# 40Ortho.net
KiCad netlist of a schematic drawn in EAGLE
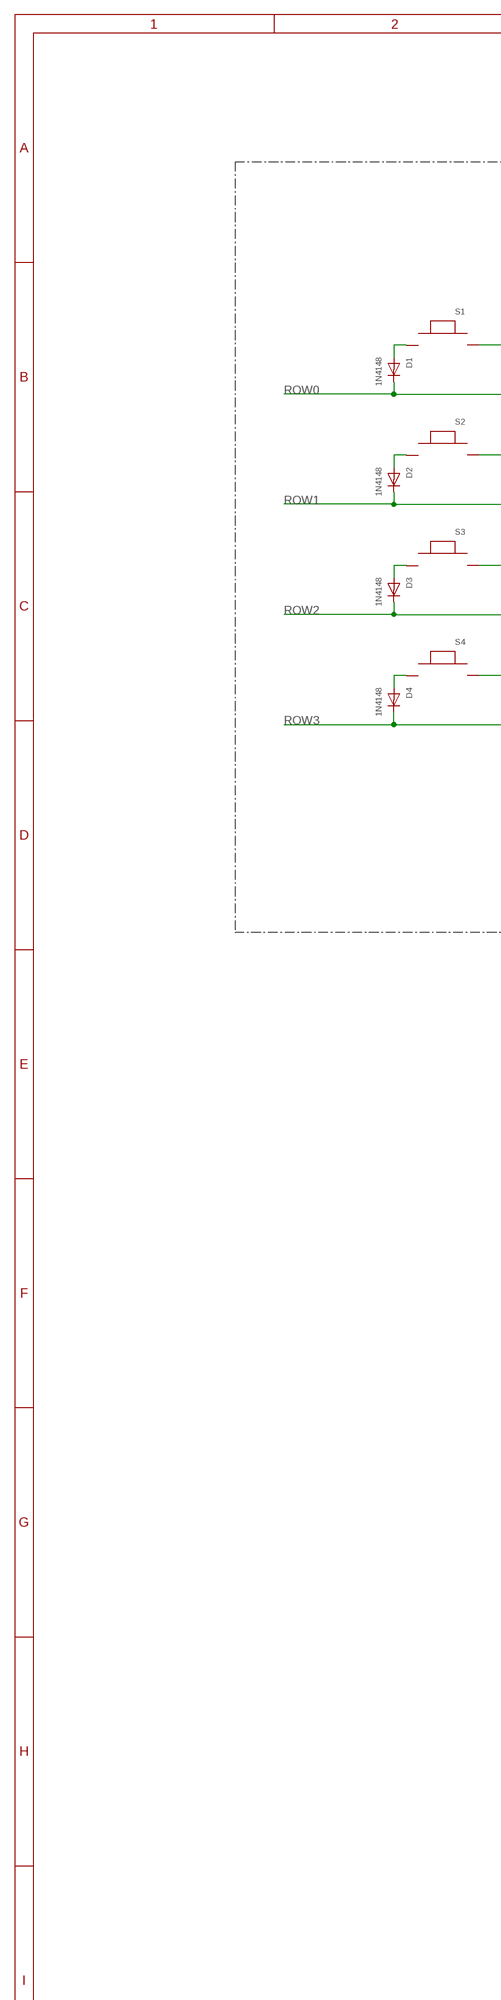
[diagram p0: schematic, sheet 1, part 1 of 2]
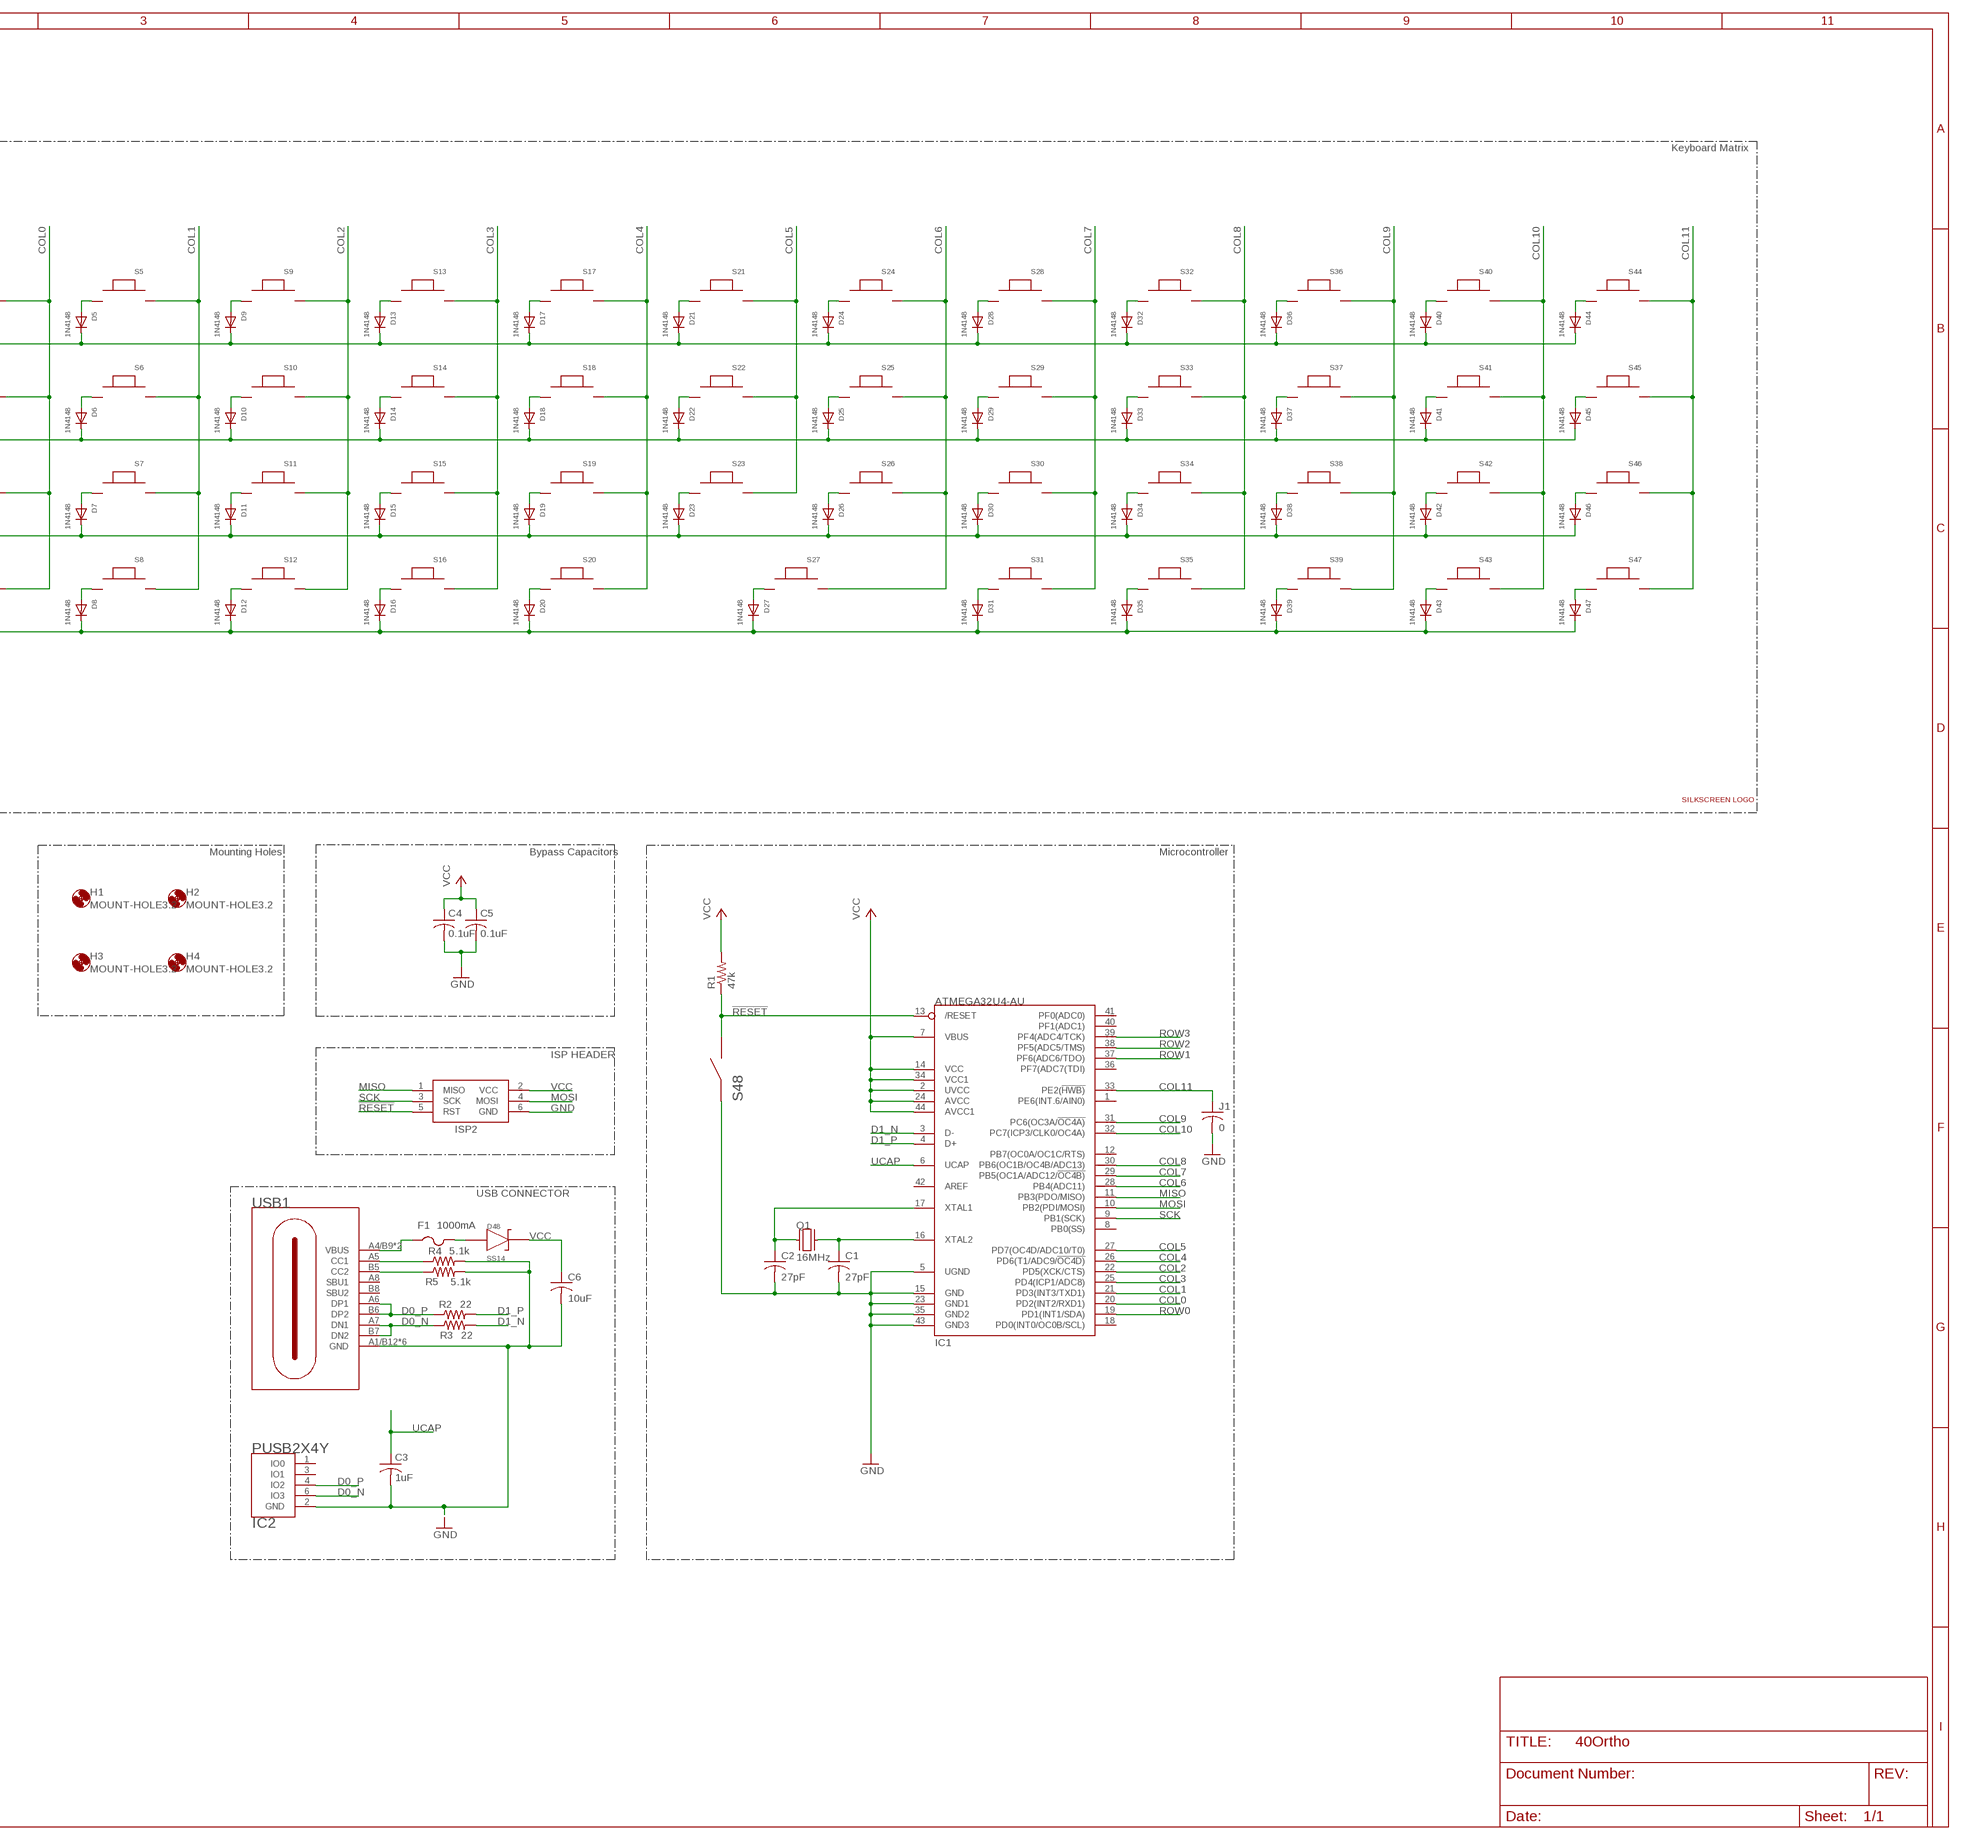
[diagram p1: schematic, sheet 1, part 2 of 2]

(export (version "E")
  (design (tool "Eeschema 10.0.6"))
  (components
    (comp (ref "C1")
      (value "27pF")
      (footprint "eagle-import:C0805")
      (libsource (lib "eagle-import") (part "C-USC0805"))
    )
    (comp (ref "C2")
      (value "27pF")
      (footprint "eagle-import:C0805")
      (libsource (lib "eagle-import") (part "C-USC0805"))
    )
    (comp (ref "C3")
      (value "1uF")
      (footprint "eagle-import:C0805")
      (libsource (lib "eagle-import") (part "C-USC0805"))
    )
    (comp (ref "C4")
      (value "0.1uF")
      (footprint "eagle-import:C0805")
      (libsource (lib "eagle-import") (part "C-USC0805"))
    )
    (comp (ref "C5")
      (value "0.1uF")
      (footprint "eagle-import:C0805")
      (libsource (lib "eagle-import") (part "C-USC0805"))
    )
    (comp (ref "C6")
      (value "10uF")
      (footprint "eagle-import:C0805")
      (libsource (lib "eagle-import") (part "C-USC0805"))
    )
    (comp (ref "D1")
      (value "1N4148")
      (footprint "eagle-import:SOD-323F")
      (fields (field (name "SPICEPREFIX") "D"))
      (libsource (lib "eagle-import") (part "DIODESOD-323F"))
    )
    (comp (ref "D2")
      (value "1N4148")
      (footprint "eagle-import:SOD-323F")
      (libsource (lib "eagle-import") (part "DIODESOD-323F"))
    )
    (comp (ref "D3")
      (value "1N4148")
      (footprint "eagle-import:SOD-323F")
      (libsource (lib "eagle-import") (part "DIODESOD-323F"))
    )
    (comp (ref "D4")
      (value "1N4148")
      (footprint "eagle-import:SOD-323F")
      (libsource (lib "eagle-import") (part "DIODESOD-323F"))
    )
    (comp (ref "D5")
      (value "1N4148")
      (footprint "eagle-import:SOD-323F")
      (libsource (lib "eagle-import") (part "DIODESOD-323F"))
    )
    (comp (ref "D6")
      (value "1N4148")
      (footprint "eagle-import:SOD-323F")
      (fields (field (name "SPICEPREFIX") "D"))
      (libsource (lib "eagle-import") (part "DIODESOD-323F"))
    )
    (comp (ref "D7")
      (value "1N4148")
      (footprint "eagle-import:SOD-323F")
      (libsource (lib "eagle-import") (part "DIODESOD-323F"))
    )
    (comp (ref "D8")
      (value "1N4148")
      (footprint "eagle-import:SOD-323F")
      (libsource (lib "eagle-import") (part "DIODESOD-323F"))
    )
    (comp (ref "D9")
      (value "1N4148")
      (footprint "eagle-import:SOD-323F")
      (libsource (lib "eagle-import") (part "DIODESOD-323F"))
    )
    (comp (ref "D10")
      (value "1N4148")
      (footprint "eagle-import:SOD-323F")
      (libsource (lib "eagle-import") (part "DIODESOD-323F"))
    )
    (comp (ref "D11")
      (value "1N4148")
      (footprint "eagle-import:SOD-323F")
      (libsource (lib "eagle-import") (part "DIODESOD-323F"))
    )
    (comp (ref "D12")
      (value "1N4148")
      (footprint "eagle-import:SOD-323F")
      (libsource (lib "eagle-import") (part "DIODESOD-323F"))
    )
    (comp (ref "D13")
      (value "1N4148")
      (footprint "eagle-import:SOD-323F")
      (libsource (lib "eagle-import") (part "DIODESOD-323F"))
    )
    (comp (ref "D14")
      (value "1N4148")
      (footprint "eagle-import:SOD-323F")
      (libsource (lib "eagle-import") (part "DIODESOD-323F"))
    )
    (comp (ref "D15")
      (value "1N4148")
      (footprint "eagle-import:SOD-323F")
      (libsource (lib "eagle-import") (part "DIODESOD-323F"))
    )
    (comp (ref "D16")
      (value "1N4148")
      (footprint "eagle-import:SOD-323F")
      (libsource (lib "eagle-import") (part "DIODESOD-323F"))
    )
    (comp (ref "D17")
      (value "1N4148")
      (footprint "eagle-import:SOD-323F")
      (libsource (lib "eagle-import") (part "DIODESOD-323F"))
    )
    (comp (ref "D18")
      (value "1N4148")
      (footprint "eagle-import:SOD-323F")
      (libsource (lib "eagle-import") (part "DIODESOD-323F"))
    )
    (comp (ref "D19")
      (value "1N4148")
      (footprint "eagle-import:SOD-323F")
      (libsource (lib "eagle-import") (part "DIODESOD-323F"))
    )
    (comp (ref "D20")
      (value "1N4148")
      (footprint "eagle-import:SOD-323F")
      (libsource (lib "eagle-import") (part "DIODESOD-323F"))
    )
    (comp (ref "D21")
      (value "1N4148")
      (footprint "eagle-import:SOD-323F")
      (libsource (lib "eagle-import") (part "DIODESOD-323F"))
    )
    (comp (ref "D22")
      (value "1N4148")
      (footprint "eagle-import:SOD-323F")
      (libsource (lib "eagle-import") (part "DIODESOD-323F"))
    )
    (comp (ref "D23")
      (value "1N4148")
      (footprint "eagle-import:SOD-323F")
      (libsource (lib "eagle-import") (part "DIODESOD-323F"))
    )
    (comp (ref "D24")
      (value "1N4148")
      (footprint "eagle-import:SOD-323F")
      (libsource (lib "eagle-import") (part "DIODESOD-323F"))
    )
    (comp (ref "D25")
      (value "1N4148")
      (footprint "eagle-import:SOD-323F")
      (libsource (lib "eagle-import") (part "DIODESOD-323F"))
    )
    (comp (ref "D26")
      (value "1N4148")
      (footprint "eagle-import:SOD-323F")
      (libsource (lib "eagle-import") (part "DIODESOD-323F"))
    )
    (comp (ref "D27")
      (value "1N4148")
      (footprint "eagle-import:SOD-323F")
      (libsource (lib "eagle-import") (part "DIODESOD-323F"))
    )
    (comp (ref "D28")
      (value "1N4148")
      (footprint "eagle-import:SOD-323F")
      (libsource (lib "eagle-import") (part "DIODESOD-323F"))
    )
    (comp (ref "D29")
      (value "1N4148")
      (footprint "eagle-import:SOD-323F")
      (libsource (lib "eagle-import") (part "DIODESOD-323F"))
    )
    (comp (ref "D30")
      (value "1N4148")
      (footprint "eagle-import:SOD-323F")
      (libsource (lib "eagle-import") (part "DIODESOD-323F"))
    )
    (comp (ref "D31")
      (value "1N4148")
      (footprint "eagle-import:SOD-323F")
      (libsource (lib "eagle-import") (part "DIODESOD-323F"))
    )
    (comp (ref "D32")
      (value "1N4148")
      (footprint "eagle-import:SOD-323F")
      (libsource (lib "eagle-import") (part "DIODESOD-323F"))
    )
    (comp (ref "D33")
      (value "1N4148")
      (footprint "eagle-import:SOD-323F")
      (libsource (lib "eagle-import") (part "DIODESOD-323F"))
    )
    (comp (ref "D34")
      (value "1N4148")
      (footprint "eagle-import:SOD-323F")
      (libsource (lib "eagle-import") (part "DIODESOD-323F"))
    )
    (comp (ref "D35")
      (value "1N4148")
      (footprint "eagle-import:SOD-323F")
      (libsource (lib "eagle-import") (part "DIODESOD-323F"))
    )
    (comp (ref "D36")
      (value "1N4148")
      (footprint "eagle-import:SOD-323F")
      (libsource (lib "eagle-import") (part "DIODESOD-323F"))
    )
    (comp (ref "D37")
      (value "1N4148")
      (footprint "eagle-import:SOD-323F")
      (libsource (lib "eagle-import") (part "DIODESOD-323F"))
    )
    (comp (ref "D38")
      (value "1N4148")
      (footprint "eagle-import:SOD-323F")
      (libsource (lib "eagle-import") (part "DIODESOD-323F"))
    )
    (comp (ref "D39")
      (value "1N4148")
      (footprint "eagle-import:SOD-323F")
      (libsource (lib "eagle-import") (part "DIODESOD-323F"))
    )
    (comp (ref "D40")
      (value "1N4148")
      (footprint "eagle-import:SOD-323F")
      (libsource (lib "eagle-import") (part "DIODESOD-323F"))
    )
    (comp (ref "D41")
      (value "1N4148")
      (footprint "eagle-import:SOD-323F")
      (libsource (lib "eagle-import") (part "DIODESOD-323F"))
    )
    (comp (ref "D42")
      (value "1N4148")
      (footprint "eagle-import:SOD-323F")
      (libsource (lib "eagle-import") (part "DIODESOD-323F"))
    )
    (comp (ref "D43")
      (value "1N4148")
      (footprint "eagle-import:SOD-323F")
      (libsource (lib "eagle-import") (part "DIODESOD-323F"))
    )
    (comp (ref "D44")
      (value "1N4148")
      (footprint "eagle-import:SOD-323F")
      (libsource (lib "eagle-import") (part "DIODESOD-323F"))
    )
    (comp (ref "D45")
      (value "1N4148")
      (footprint "eagle-import:SOD-323F")
      (libsource (lib "eagle-import") (part "DIODESOD-323F"))
    )
    (comp (ref "D46")
      (value "1N4148")
      (footprint "eagle-import:SOD-323F")
      (libsource (lib "eagle-import") (part "DIODESOD-323F"))
    )
    (comp (ref "D47")
      (value "1N4148")
      (footprint "eagle-import:SOD-323F")
      (libsource (lib "eagle-import") (part "DIODESOD-323F"))
    )
    (comp (ref "D48")
      (value "SS14")
      (footprint "eagle-import:DO-214AC")
      (libsource (lib "eagle-import") (part "SS14"))
    )
    (comp (ref "F1")
      (value "1000mA")
      (footprint "eagle-import:R1206")
      (libsource (lib "eagle-import") (part "PTCFUSE-1206"))
    )
    (comp (ref "H1")
      (value "MOUNT-HOLE3.2")
      (footprint "eagle-import:3,2")
      (libsource (lib "eagle-import") (part "MOUNT-HOLE3.2"))
    )
    (comp (ref "H2")
      (value "MOUNT-HOLE3.2")
      (footprint "eagle-import:3,2")
      (libsource (lib "eagle-import") (part "MOUNT-HOLE3.2"))
    )
    (comp (ref "H3")
      (value "MOUNT-HOLE3.2")
      (footprint "eagle-import:3,2")
      (libsource (lib "eagle-import") (part "MOUNT-HOLE3.2"))
    )
    (comp (ref "H4")
      (value "MOUNT-HOLE3.2")
      (footprint "eagle-import:3,2")
      (libsource (lib "eagle-import") (part "MOUNT-HOLE3.2"))
    )
    (comp (ref "IC1")
      (value "ATMEGA32U4-AU")
      (footprint "eagle-import:TQFP44")
      (libsource (lib "eagle-import") (part "ATMEGA32U4-AU"))
    )
    (comp (ref "IC2")
      (value "PUSB2X4Y")
      (footprint "eagle-import:SOT363")
      (libsource (lib "eagle-import") (part "PUSB2X4Y"))
    )
    (comp (ref "ISP2")
      (value "AVRISP-6")
      (footprint "eagle-import:AVRISP")
      (libsource (lib "eagle-import") (part "AVRISP-6"))
    )
    (comp (ref "J1")
      (value "0")
      (footprint "eagle-import:C0805")
      (libsource (lib "eagle-import") (part "C-USC0805"))
    )
    (comp (ref "Q1")
      (value "16MHz")
      (footprint "eagle-import:ABLS7M2")
      (libsource (lib "eagle-import") (part "ABLS7M2"))
    )
    (comp (ref "R1")
      (value "47k")
      (footprint "eagle-import:R0805")
      (libsource (lib "eagle-import") (part "R-US_R0805"))
    )
    (comp (ref "R2")
      (value "22")
      (footprint "eagle-import:R0805")
      (libsource (lib "eagle-import") (part "R-US_R0805"))
    )
    (comp (ref "R3")
      (value "22")
      (footprint "eagle-import:R0805")
      (libsource (lib "eagle-import") (part "R-US_R0805"))
    )
    (comp (ref "R4")
      (value "5.1k")
      (footprint "eagle-import:R0805")
      (libsource (lib "eagle-import") (part "R-US_R0805"))
    )
    (comp (ref "R5")
      (value "5.1k")
      (footprint "eagle-import:R0805")
      (libsource (lib "eagle-import") (part "R-US_R0805"))
    )
    (comp (ref "S1")
      (value "MX_SMD_1U")
      (footprint "eagle-import:MX_SMD")
      (libsource (lib "eagle-import") (part "MX_SMD_1U"))
    )
    (comp (ref "S2")
      (value "MX_SMD_1U")
      (footprint "eagle-import:MX_SMD")
      (libsource (lib "eagle-import") (part "MX_SMD_1U"))
    )
    (comp (ref "S3")
      (value "MX_SMD_1U")
      (footprint "eagle-import:MX_SMD")
      (libsource (lib "eagle-import") (part "MX_SMD_1U"))
    )
    (comp (ref "S4")
      (value "MX_SMD_1U")
      (footprint "eagle-import:MX_SMD")
      (libsource (lib "eagle-import") (part "MX_SMD_1U"))
    )
    (comp (ref "S5")
      (value "MX_SMD_1U")
      (footprint "eagle-import:MX_SMD")
      (libsource (lib "eagle-import") (part "MX_SMD_1U"))
    )
    (comp (ref "S6")
      (value "MX_SMD_1U")
      (footprint "eagle-import:MX_SMD")
      (libsource (lib "eagle-import") (part "MX_SMD_1U"))
    )
    (comp (ref "S7")
      (value "MX_SMD_1U")
      (footprint "eagle-import:MX_SMD")
      (libsource (lib "eagle-import") (part "MX_SMD_1U"))
    )
    (comp (ref "S8")
      (value "MX_SMD_1U")
      (footprint "eagle-import:MX_SMD")
      (libsource (lib "eagle-import") (part "MX_SMD_1U"))
    )
    (comp (ref "S9")
      (value "MX_SMD_1U")
      (footprint "eagle-import:MX_SMD")
      (libsource (lib "eagle-import") (part "MX_SMD_1U"))
    )
    (comp (ref "S10")
      (value "MX_SMD_1U")
      (footprint "eagle-import:MX_SMD")
      (libsource (lib "eagle-import") (part "MX_SMD_1U"))
    )
    (comp (ref "S11")
      (value "MX_SMD_1U")
      (footprint "eagle-import:MX_SMD")
      (libsource (lib "eagle-import") (part "MX_SMD_1U"))
    )
    (comp (ref "S12")
      (value "MX_SMD_1U")
      (footprint "eagle-import:MX_SMD")
      (libsource (lib "eagle-import") (part "MX_SMD_1U"))
    )
    (comp (ref "S13")
      (value "MX_SMD_1U")
      (footprint "eagle-import:MX_SMD")
      (libsource (lib "eagle-import") (part "MX_SMD_1U"))
    )
    (comp (ref "S14")
      (value "MX_SMD_1U")
      (footprint "eagle-import:MX_SMD")
      (libsource (lib "eagle-import") (part "MX_SMD_1U"))
    )
    (comp (ref "S15")
      (value "MX_SMD_1U")
      (footprint "eagle-import:MX_SMD")
      (libsource (lib "eagle-import") (part "MX_SMD_1U"))
    )
    (comp (ref "S16")
      (value "MX_SMD_1U")
      (footprint "eagle-import:MX_SMD")
      (libsource (lib "eagle-import") (part "MX_SMD_1U"))
    )
    (comp (ref "S17")
      (value "MX_SMD_1U")
      (footprint "eagle-import:MX_SMD")
      (libsource (lib "eagle-import") (part "MX_SMD_1U"))
    )
    (comp (ref "S18")
      (value "MX_SMD_1U")
      (footprint "eagle-import:MX_SMD")
      (libsource (lib "eagle-import") (part "MX_SMD_1U"))
    )
    (comp (ref "S19")
      (value "MX_SMD_1U")
      (footprint "eagle-import:MX_SMD")
      (libsource (lib "eagle-import") (part "MX_SMD_1U"))
    )
    (comp (ref "S20")
      (value "MX_SMD_1U")
      (footprint "eagle-import:MX_SMD")
      (libsource (lib "eagle-import") (part "MX_SMD_1U"))
    )
    (comp (ref "S21")
      (value "MX_SMD_1U")
      (footprint "eagle-import:MX_SMD")
      (libsource (lib "eagle-import") (part "MX_SMD_1U"))
    )
    (comp (ref "S22")
      (value "MX_SMD_1U")
      (footprint "eagle-import:MX_SMD")
      (libsource (lib "eagle-import") (part "MX_SMD_1U"))
    )
    (comp (ref "S23")
      (value "MX_SMD_1U")
      (footprint "eagle-import:MX_SMD")
      (libsource (lib "eagle-import") (part "MX_SMD_1U"))
    )
    (comp (ref "S24")
      (value "MX_SMD_1U")
      (footprint "eagle-import:MX_SMD")
      (libsource (lib "eagle-import") (part "MX_SMD_1U"))
    )
    (comp (ref "S25")
      (value "MX_SMD_1U")
      (footprint "eagle-import:MX_SMD")
      (libsource (lib "eagle-import") (part "MX_SMD_1U"))
    )
    (comp (ref "S26")
      (value "MX_SMD_1U")
      (footprint "eagle-import:MX_SMD")
      (libsource (lib "eagle-import") (part "MX_SMD_1U"))
    )
    (comp (ref "S27")
      (value "MX_SMD_2UH")
      (footprint "eagle-import:MX_SMD2U")
      (libsource (lib "eagle-import") (part "MX_SMD_2UH"))
    )
    (comp (ref "S28")
      (value "MX_SMD_1U")
      (footprint "eagle-import:MX_SMD")
      (libsource (lib "eagle-import") (part "MX_SMD_1U"))
    )
    (comp (ref "S29")
      (value "MX_SMD_1U")
      (footprint "eagle-import:MX_SMD")
      (libsource (lib "eagle-import") (part "MX_SMD_1U"))
    )
    (comp (ref "S30")
      (value "MX_SMD_1U")
      (footprint "eagle-import:MX_SMD")
      (libsource (lib "eagle-import") (part "MX_SMD_1U"))
    )
    (comp (ref "S31")
      (value "MX_SMD_1U")
      (footprint "eagle-import:MX_SMD")
      (libsource (lib "eagle-import") (part "MX_SMD_1U"))
    )
    (comp (ref "S32")
      (value "MX_SMD_1U")
      (footprint "eagle-import:MX_SMD")
      (libsource (lib "eagle-import") (part "MX_SMD_1U"))
    )
    (comp (ref "S33")
      (value "MX_SMD_1U")
      (footprint "eagle-import:MX_SMD")
      (libsource (lib "eagle-import") (part "MX_SMD_1U"))
    )
    (comp (ref "S34")
      (value "MX_SMD_1U")
      (footprint "eagle-import:MX_SMD")
      (libsource (lib "eagle-import") (part "MX_SMD_1U"))
    )
    (comp (ref "S35")
      (value "MX_SMD_1U")
      (footprint "eagle-import:MX_SMD")
      (libsource (lib "eagle-import") (part "MX_SMD_1U"))
    )
    (comp (ref "S36")
      (value "MX_SMD_1U")
      (footprint "eagle-import:MX_SMD")
      (libsource (lib "eagle-import") (part "MX_SMD_1U"))
    )
    (comp (ref "S37")
      (value "MX_SMD_1U")
      (footprint "eagle-import:MX_SMD")
      (libsource (lib "eagle-import") (part "MX_SMD_1U"))
    )
    (comp (ref "S38")
      (value "MX_SMD_1U")
      (footprint "eagle-import:MX_SMD")
      (libsource (lib "eagle-import") (part "MX_SMD_1U"))
    )
    (comp (ref "S39")
      (value "MX_SMD_1U")
      (footprint "eagle-import:MX_SMD")
      (libsource (lib "eagle-import") (part "MX_SMD_1U"))
    )
    (comp (ref "S40")
      (value "MX_SMD_1U")
      (footprint "eagle-import:MX_SMD")
      (libsource (lib "eagle-import") (part "MX_SMD_1U"))
    )
    (comp (ref "S41")
      (value "MX_SMD_1U")
      (footprint "eagle-import:MX_SMD")
      (libsource (lib "eagle-import") (part "MX_SMD_1U"))
    )
    (comp (ref "S42")
      (value "MX_SMD_1U")
      (footprint "eagle-import:MX_SMD")
      (libsource (lib "eagle-import") (part "MX_SMD_1U"))
    )
    (comp (ref "S43")
      (value "MX_SMD_1U")
      (footprint "eagle-import:MX_SMD")
      (libsource (lib "eagle-import") (part "MX_SMD_1U"))
    )
    (comp (ref "S44")
      (value "MX_SMD_1U")
      (footprint "eagle-import:MX_SMD")
      (libsource (lib "eagle-import") (part "MX_SMD_1U"))
    )
    (comp (ref "S45")
      (value "MX_SMD_1U")
      (footprint "eagle-import:MX_SMD")
      (libsource (lib "eagle-import") (part "MX_SMD_1U"))
    )
    (comp (ref "S46")
      (value "MX_SMD_1U")
      (footprint "eagle-import:MX_SMD")
      (libsource (lib "eagle-import") (part "MX_SMD_1U"))
    )
    (comp (ref "S47")
      (value "MX_SMD_1U")
      (footprint "eagle-import:MX_SMD")
      (libsource (lib "eagle-import") (part "MX_SMD_1U"))
    )
    (comp (ref "S48")
      (value "B3U-1000P")
      (footprint "eagle-import:B3U-1000P")
      (libsource (lib "eagle-import") (part "B3U-1000P"))
    )
    (comp (ref "U$1")
      (value "LOGO")
      (footprint "eagle-import:LOGO")
      (libsource (lib "eagle-import") (part "LOGO"))
    )
    (comp (ref "USB1")
      (value "USBC_16PINSMD")
      (footprint "eagle-import:USBC_16PINSMD")
      (libsource (lib "eagle-import") (part "USBC_16PINSMD"))
    )
  )
  (nets
    (net (code "1") (name "/COL0") (class "Default")
      (node (ref "IC1") (pin "20") (pinfunction "PD2(INT2/RXD1)_20") (pintype "bidirectional"))
      (node (ref "S1") (pin "P$2") (pinfunction "P$2_P$2") (pintype "bidirectional"))
      (node (ref "S2") (pin "P$2") (pinfunction "P$2_P$2") (pintype "bidirectional"))
      (node (ref "S3") (pin "P$2") (pinfunction "P$2_P$2") (pintype "bidirectional"))
      (node (ref "S4") (pin "P$2") (pinfunction "P$2_P$2") (pintype "bidirectional"))
    )
    (net (code "2") (name "/COL1") (class "Default")
      (node (ref "IC1") (pin "21") (pinfunction "PD3(INT3/TXD1)_21") (pintype "bidirectional"))
      (node (ref "S5") (pin "P$2") (pinfunction "P$2_P$2") (pintype "bidirectional"))
      (node (ref "S6") (pin "P$2") (pinfunction "P$2_P$2") (pintype "bidirectional"))
      (node (ref "S7") (pin "P$2") (pinfunction "P$2_P$2") (pintype "bidirectional"))
      (node (ref "S8") (pin "P$2") (pinfunction "P$2_P$2") (pintype "bidirectional"))
    )
    (net (code "3") (name "/COL2") (class "Default")
      (node (ref "IC1") (pin "22") (pinfunction "PD5(XCK/CTS)_22") (pintype "bidirectional"))
      (node (ref "S10") (pin "P$2") (pinfunction "P$2_P$2") (pintype "bidirectional"))
      (node (ref "S11") (pin "P$2") (pinfunction "P$2_P$2") (pintype "bidirectional"))
      (node (ref "S12") (pin "P$2") (pinfunction "P$2_P$2") (pintype "bidirectional"))
      (node (ref "S9") (pin "P$2") (pinfunction "P$2_P$2") (pintype "bidirectional"))
    )
    (net (code "4") (name "/COL3") (class "Default")
      (node (ref "IC1") (pin "25") (pinfunction "PD4(ICP1/ADC8)_25") (pintype "bidirectional"))
      (node (ref "S13") (pin "P$2") (pinfunction "P$2_P$2") (pintype "bidirectional"))
      (node (ref "S14") (pin "P$2") (pinfunction "P$2_P$2") (pintype "bidirectional"))
      (node (ref "S15") (pin "P$2") (pinfunction "P$2_P$2") (pintype "bidirectional"))
      (node (ref "S16") (pin "P$2") (pinfunction "P$2_P$2") (pintype "bidirectional"))
    )
    (net (code "5") (name "/COL4") (class "Default")
      (node (ref "IC1") (pin "26") (pinfunction "PD6(T1/ADC9/~{OC4D})_26") (pintype "bidirectional"))
      (node (ref "S17") (pin "P$2") (pinfunction "P$2_P$2") (pintype "bidirectional"))
      (node (ref "S18") (pin "P$2") (pinfunction "P$2_P$2") (pintype "bidirectional"))
      (node (ref "S19") (pin "P$2") (pinfunction "P$2_P$2") (pintype "bidirectional"))
      (node (ref "S20") (pin "P$2") (pinfunction "P$2_P$2") (pintype "bidirectional"))
    )
    (net (code "6") (name "/COL5") (class "Default")
      (node (ref "IC1") (pin "27") (pinfunction "PD7(OC4D/ADC10/T0)_27") (pintype "bidirectional"))
      (node (ref "S21") (pin "P$2") (pinfunction "P$2_P$2") (pintype "bidirectional"))
      (node (ref "S22") (pin "P$2") (pinfunction "P$2_P$2") (pintype "bidirectional"))
      (node (ref "S23") (pin "P$2") (pinfunction "P$2_P$2") (pintype "bidirectional"))
    )
    (net (code "7") (name "/COL6") (class "Default")
      (node (ref "IC1") (pin "28") (pinfunction "PB4(ADC11)_28") (pintype "bidirectional"))
      (node (ref "S24") (pin "P$2") (pinfunction "P$2_P$2") (pintype "bidirectional"))
      (node (ref "S25") (pin "P$2") (pinfunction "P$2_P$2") (pintype "bidirectional"))
      (node (ref "S26") (pin "P$2") (pinfunction "P$2_P$2") (pintype "bidirectional"))
      (node (ref "S27") (pin "P$2") (pinfunction "P$2_P$2") (pintype "bidirectional"))
    )
    (net (code "8") (name "/COL7") (class "Default")
      (node (ref "IC1") (pin "29") (pinfunction "PB5(OC1A/ADC12/~{OC4B})_29") (pintype "bidirectional"))
      (node (ref "S28") (pin "P$2") (pinfunction "P$2_P$2") (pintype "bidirectional"))
      (node (ref "S29") (pin "P$2") (pinfunction "P$2_P$2") (pintype "bidirectional"))
      (node (ref "S30") (pin "P$2") (pinfunction "P$2_P$2") (pintype "bidirectional"))
      (node (ref "S31") (pin "P$2") (pinfunction "P$2_P$2") (pintype "bidirectional"))
    )
    (net (code "9") (name "/COL8") (class "Default")
      (node (ref "IC1") (pin "30") (pinfunction "PB6(OC1B/OC4B/ADC13)_30") (pintype "bidirectional"))
      (node (ref "S32") (pin "P$2") (pinfunction "P$2_P$2") (pintype "bidirectional"))
      (node (ref "S33") (pin "P$2") (pinfunction "P$2_P$2") (pintype "bidirectional"))
      (node (ref "S34") (pin "P$2") (pinfunction "P$2_P$2") (pintype "bidirectional"))
      (node (ref "S35") (pin "P$2") (pinfunction "P$2_P$2") (pintype "bidirectional"))
    )
    (net (code "10") (name "/COL9") (class "Default")
      (node (ref "IC1") (pin "31") (pinfunction "PC6(OC3A/~{OC4A})_31") (pintype "bidirectional"))
      (node (ref "S36") (pin "P$2") (pinfunction "P$2_P$2") (pintype "bidirectional"))
      (node (ref "S37") (pin "P$2") (pinfunction "P$2_P$2") (pintype "bidirectional"))
      (node (ref "S38") (pin "P$2") (pinfunction "P$2_P$2") (pintype "bidirectional"))
      (node (ref "S39") (pin "P$2") (pinfunction "P$2_P$2") (pintype "bidirectional"))
    )
    (net (code "11") (name "/COL10") (class "Default")
      (node (ref "IC1") (pin "32") (pinfunction "PC7(ICP3/CLK0/OC4A)_32") (pintype "bidirectional"))
      (node (ref "S40") (pin "P$2") (pinfunction "P$2_P$2") (pintype "bidirectional"))
      (node (ref "S41") (pin "P$2") (pinfunction "P$2_P$2") (pintype "bidirectional"))
      (node (ref "S42") (pin "P$2") (pinfunction "P$2_P$2") (pintype "bidirectional"))
      (node (ref "S43") (pin "P$2") (pinfunction "P$2_P$2") (pintype "bidirectional"))
    )
    (net (code "12") (name "/COL11") (class "Default")
      (node (ref "IC1") (pin "33") (pinfunction "PE2(~{HWB})_33") (pintype "bidirectional"))
      (node (ref "J1") (pin "1") (pinfunction "1_1") (pintype "passive"))
      (node (ref "S44") (pin "P$2") (pinfunction "P$2_P$2") (pintype "bidirectional"))
      (node (ref "S45") (pin "P$2") (pinfunction "P$2_P$2") (pintype "bidirectional"))
      (node (ref "S46") (pin "P$2") (pinfunction "P$2_P$2") (pintype "bidirectional"))
      (node (ref "S47") (pin "P$2") (pinfunction "P$2_P$2") (pintype "bidirectional"))
    )
    (net (code "13") (name "/D0_N") (class "Default")
      (node (ref "IC2") (pin "6") (pinfunction "IO3_6") (pintype "bidirectional"))
      (node (ref "R3") (pin "1") (pinfunction "1_1") (pintype "passive"))
      (node (ref "USB1") (pin "A7") (pinfunction "DN1_A7") (pintype "bidirectional"))
      (node (ref "USB1") (pin "B7") (pinfunction "DN2_B7") (pintype "bidirectional"))
    )
    (net (code "14") (name "/D0_P") (class "Default")
      (node (ref "IC2") (pin "4") (pinfunction "IO2_4") (pintype "bidirectional"))
      (node (ref "R2") (pin "1") (pinfunction "1_1") (pintype "passive"))
      (node (ref "USB1") (pin "A6") (pinfunction "DP1_A6") (pintype "bidirectional"))
      (node (ref "USB1") (pin "B6") (pinfunction "DP2_B6") (pintype "bidirectional"))
    )
    (net (code "15") (name "/D1_N") (class "Default")
      (node (ref "IC1") (pin "3") (pinfunction "D-_3") (pintype "bidirectional"))
      (node (ref "R3") (pin "2") (pinfunction "2_2") (pintype "passive"))
    )
    (net (code "16") (name "/D1_P") (class "Default")
      (node (ref "IC1") (pin "4") (pinfunction "D+_4") (pintype "bidirectional"))
      (node (ref "R2") (pin "2") (pinfunction "2_2") (pintype "passive"))
    )
    (net (code "17") (name "/MISO") (class "Default")
      (node (ref "IC1") (pin "11") (pinfunction "PB3(PDO/MISO)_11") (pintype "bidirectional"))
      (node (ref "ISP2") (pin "1") (pinfunction "MISO_1") (pintype "input"))
    )
    (net (code "18") (name "/MOSI") (class "Default")
      (node (ref "IC1") (pin "10") (pinfunction "PB2(PDI/MOSI)_10") (pintype "bidirectional"))
      (node (ref "ISP2") (pin "4") (pinfunction "MOSI_4") (pintype "output"))
    )
    (net (code "19") (name "/ROW0") (class "Default")
      (node (ref "D1") (pin "C") (pinfunction "C_C") (pintype "passive"))
      (node (ref "D13") (pin "C") (pinfunction "C_C") (pintype "passive"))
      (node (ref "D17") (pin "C") (pinfunction "C_C") (pintype "passive"))
      (node (ref "D21") (pin "C") (pinfunction "C_C") (pintype "passive"))
      (node (ref "D24") (pin "C") (pinfunction "C_C") (pintype "passive"))
      (node (ref "D28") (pin "C") (pinfunction "C_C") (pintype "passive"))
      (node (ref "D32") (pin "C") (pinfunction "C_C") (pintype "passive"))
      (node (ref "D36") (pin "C") (pinfunction "C_C") (pintype "passive"))
      (node (ref "D40") (pin "C") (pinfunction "C_C") (pintype "passive"))
      (node (ref "D44") (pin "C") (pinfunction "C_C") (pintype "passive"))
      (node (ref "D5") (pin "C") (pinfunction "C_C") (pintype "passive"))
      (node (ref "D9") (pin "C") (pinfunction "C_C") (pintype "passive"))
      (node (ref "IC1") (pin "19") (pinfunction "PD1(INT1/SDA)_19") (pintype "bidirectional"))
    )
    (net (code "20") (name "/ROW1") (class "Default")
      (node (ref "D10") (pin "C") (pinfunction "C_C") (pintype "passive"))
      (node (ref "D14") (pin "C") (pinfunction "C_C") (pintype "passive"))
      (node (ref "D18") (pin "C") (pinfunction "C_C") (pintype "passive"))
      (node (ref "D2") (pin "C") (pinfunction "C_C") (pintype "passive"))
      (node (ref "D22") (pin "C") (pinfunction "C_C") (pintype "passive"))
      (node (ref "D25") (pin "C") (pinfunction "C_C") (pintype "passive"))
      (node (ref "D29") (pin "C") (pinfunction "C_C") (pintype "passive"))
      (node (ref "D33") (pin "C") (pinfunction "C_C") (pintype "passive"))
      (node (ref "D37") (pin "C") (pinfunction "C_C") (pintype "passive"))
      (node (ref "D41") (pin "C") (pinfunction "C_C") (pintype "passive"))
      (node (ref "D45") (pin "C") (pinfunction "C_C") (pintype "passive"))
      (node (ref "D6") (pin "C") (pinfunction "C_C") (pintype "passive"))
      (node (ref "IC1") (pin "37") (pinfunction "PF6(ADC6/TDO)_37") (pintype "bidirectional"))
    )
    (net (code "21") (name "/ROW2") (class "Default")
      (node (ref "D11") (pin "C") (pinfunction "C_C") (pintype "passive"))
      (node (ref "D15") (pin "C") (pinfunction "C_C") (pintype "passive"))
      (node (ref "D19") (pin "C") (pinfunction "C_C") (pintype "passive"))
      (node (ref "D23") (pin "C") (pinfunction "C_C") (pintype "passive"))
      (node (ref "D26") (pin "C") (pinfunction "C_C") (pintype "passive"))
      (node (ref "D3") (pin "C") (pinfunction "C_C") (pintype "passive"))
      (node (ref "D30") (pin "C") (pinfunction "C_C") (pintype "passive"))
      (node (ref "D34") (pin "C") (pinfunction "C_C") (pintype "passive"))
      (node (ref "D38") (pin "C") (pinfunction "C_C") (pintype "passive"))
      (node (ref "D42") (pin "C") (pinfunction "C_C") (pintype "passive"))
      (node (ref "D46") (pin "C") (pinfunction "C_C") (pintype "passive"))
      (node (ref "D7") (pin "C") (pinfunction "C_C") (pintype "passive"))
      (node (ref "IC1") (pin "38") (pinfunction "PF5(ADC5/TMS)_38") (pintype "bidirectional"))
    )
    (net (code "22") (name "/ROW3") (class "Default")
      (node (ref "D12") (pin "C") (pinfunction "C_C") (pintype "passive"))
      (node (ref "D16") (pin "C") (pinfunction "C_C") (pintype "passive"))
      (node (ref "D20") (pin "C") (pinfunction "C_C") (pintype "passive"))
      (node (ref "D27") (pin "C") (pinfunction "C_C") (pintype "passive"))
      (node (ref "D31") (pin "C") (pinfunction "C_C") (pintype "passive"))
      (node (ref "D35") (pin "C") (pinfunction "C_C") (pintype "passive"))
      (node (ref "D39") (pin "C") (pinfunction "C_C") (pintype "passive"))
      (node (ref "D4") (pin "C") (pinfunction "C_C") (pintype "passive"))
      (node (ref "D43") (pin "C") (pinfunction "C_C") (pintype "passive"))
      (node (ref "D47") (pin "C") (pinfunction "C_C") (pintype "passive"))
      (node (ref "D8") (pin "C") (pinfunction "C_C") (pintype "passive"))
      (node (ref "IC1") (pin "39") (pinfunction "PF4(ADC4/TCK)_39") (pintype "bidirectional"))
    )
    (net (code "23") (name "/SCK") (class "Default")
      (node (ref "IC1") (pin "9") (pinfunction "PB1(SCK)_9") (pintype "bidirectional"))
      (node (ref "ISP2") (pin "3") (pinfunction "SCK_3") (pintype "output"))
    )
    (net (code "24") (name "/UCAP") (class "Default")
      (node (ref "C3") (pin "1") (pinfunction "1_1") (pintype "passive"))
      (node (ref "IC1") (pin "6") (pinfunction "UCAP_6") (pintype "bidirectional"))
    )
    (net (code "25") (name "/~{RESET}") (class "Default")
      (node (ref "IC1") (pin "13") (pinfunction "/RESET_13") (pintype "bidirectional"))
      (node (ref "ISP2") (pin "5") (pinfunction "RST_5") (pintype "output"))
      (node (ref "R1") (pin "1") (pinfunction "1_1") (pintype "passive"))
      (node (ref "S48") (pin "2") (pinfunction "P$2_2") (pintype "bidirectional"))
    )
    (net (code "26") (name "GND") (class "Default")
      (node (ref "C1") (pin "2") (pinfunction "2_2") (pintype "passive"))
      (node (ref "C2") (pin "2") (pinfunction "2_2") (pintype "passive"))
      (node (ref "C3") (pin "2") (pinfunction "2_2") (pintype "passive"))
      (node (ref "C4") (pin "2") (pinfunction "2_2") (pintype "passive"))
      (node (ref "C5") (pin "2") (pinfunction "2_2") (pintype "passive"))
      (node (ref "C6") (pin "2") (pinfunction "2_2") (pintype "passive"))
      (node (ref "IC1") (pin "15") (pinfunction "GND_15") (pintype "bidirectional"))
      (node (ref "IC1") (pin "23") (pinfunction "GND1_23") (pintype "bidirectional"))
      (node (ref "IC1") (pin "35") (pinfunction "GND2_35") (pintype "bidirectional"))
      (node (ref "IC1") (pin "43") (pinfunction "GND3_43") (pintype "bidirectional"))
      (node (ref "IC1") (pin "5") (pinfunction "UGND_5") (pintype "bidirectional"))
      (node (ref "IC2") (pin "2") (pinfunction "GND_2") (pintype "power_in"))
      (node (ref "ISP2") (pin "6") (pinfunction "GND_6") (pintype "power_in"))
      (node (ref "J1") (pin "2") (pinfunction "2_2") (pintype "passive"))
      (node (ref "R4") (pin "2") (pinfunction "2_2") (pintype "passive"))
      (node (ref "R5") (pin "2") (pinfunction "2_2") (pintype "passive"))
      (node (ref "S48") (pin "1") (pinfunction "P$1_1") (pintype "bidirectional"))
      (node (ref "USB1") (pin "A1/B12") (pinfunction "GND_A1/B12") (pintype "power_in"))
      (node (ref "USB1") (pin "B1/A12") (pinfunction "GND_B1/A12") (pintype "power_in"))
      (node (ref "USB1") (pin "GND@1") (pinfunction "GND_GND@1") (pintype "power_in"))
      (node (ref "USB1") (pin "GND@2") (pinfunction "GND_GND@2") (pintype "power_in"))
      (node (ref "USB1") (pin "GND@3") (pinfunction "GND_GND@3") (pintype "power_in"))
      (node (ref "USB1") (pin "GND@4") (pinfunction "GND_GND@4") (pintype "power_in"))
    )
    (net (code "27") (name "Net-(D1-PadA)") (class "Default")
      (node (ref "D1") (pin "A") (pinfunction "A_A") (pintype "passive"))
      (node (ref "S1") (pin "P$1") (pinfunction "P$1_P$1") (pintype "bidirectional"))
    )
    (net (code "28") (name "Net-(D2-PadA)") (class "Default")
      (node (ref "D2") (pin "A") (pinfunction "A_A") (pintype "passive"))
      (node (ref "S2") (pin "P$1") (pinfunction "P$1_P$1") (pintype "bidirectional"))
    )
    (net (code "29") (name "Net-(D3-PadA)") (class "Default")
      (node (ref "D3") (pin "A") (pinfunction "A_A") (pintype "passive"))
      (node (ref "S3") (pin "P$1") (pinfunction "P$1_P$1") (pintype "bidirectional"))
    )
    (net (code "30") (name "Net-(D4-PadA)") (class "Default")
      (node (ref "D4") (pin "A") (pinfunction "A_A") (pintype "passive"))
      (node (ref "S4") (pin "P$1") (pinfunction "P$1_P$1") (pintype "bidirectional"))
    )
    (net (code "31") (name "Net-(D5-PadA)") (class "Default")
      (node (ref "D5") (pin "A") (pinfunction "A_A") (pintype "passive"))
      (node (ref "S5") (pin "P$1") (pinfunction "P$1_P$1") (pintype "bidirectional"))
    )
    (net (code "32") (name "Net-(D6-PadA)") (class "Default")
      (node (ref "D6") (pin "A") (pinfunction "A_A") (pintype "passive"))
      (node (ref "S6") (pin "P$1") (pinfunction "P$1_P$1") (pintype "bidirectional"))
    )
    (net (code "33") (name "Net-(D7-PadA)") (class "Default")
      (node (ref "D7") (pin "A") (pinfunction "A_A") (pintype "passive"))
      (node (ref "S7") (pin "P$1") (pinfunction "P$1_P$1") (pintype "bidirectional"))
    )
    (net (code "34") (name "Net-(D8-PadA)") (class "Default")
      (node (ref "D8") (pin "A") (pinfunction "A_A") (pintype "passive"))
      (node (ref "S8") (pin "P$1") (pinfunction "P$1_P$1") (pintype "bidirectional"))
    )
    (net (code "35") (name "Net-(D9-PadA)") (class "Default")
      (node (ref "D9") (pin "A") (pinfunction "A_A") (pintype "passive"))
      (node (ref "S9") (pin "P$1") (pinfunction "P$1_P$1") (pintype "bidirectional"))
    )
    (net (code "36") (name "Net-(D10-PadA)") (class "Default")
      (node (ref "D10") (pin "A") (pinfunction "A_A") (pintype "passive"))
      (node (ref "S10") (pin "P$1") (pinfunction "P$1_P$1") (pintype "bidirectional"))
    )
    (net (code "37") (name "Net-(D11-PadA)") (class "Default")
      (node (ref "D11") (pin "A") (pinfunction "A_A") (pintype "passive"))
      (node (ref "S11") (pin "P$1") (pinfunction "P$1_P$1") (pintype "bidirectional"))
    )
    (net (code "38") (name "Net-(D12-PadA)") (class "Default")
      (node (ref "D12") (pin "A") (pinfunction "A_A") (pintype "passive"))
      (node (ref "S12") (pin "P$1") (pinfunction "P$1_P$1") (pintype "bidirectional"))
    )
    (net (code "39") (name "Net-(D13-PadA)") (class "Default")
      (node (ref "D13") (pin "A") (pinfunction "A_A") (pintype "passive"))
      (node (ref "S13") (pin "P$1") (pinfunction "P$1_P$1") (pintype "bidirectional"))
    )
    (net (code "40") (name "Net-(D14-PadA)") (class "Default")
      (node (ref "D14") (pin "A") (pinfunction "A_A") (pintype "passive"))
      (node (ref "S14") (pin "P$1") (pinfunction "P$1_P$1") (pintype "bidirectional"))
    )
    (net (code "41") (name "Net-(D15-PadA)") (class "Default")
      (node (ref "D15") (pin "A") (pinfunction "A_A") (pintype "passive"))
      (node (ref "S15") (pin "P$1") (pinfunction "P$1_P$1") (pintype "bidirectional"))
    )
    (net (code "42") (name "Net-(D16-PadA)") (class "Default")
      (node (ref "D16") (pin "A") (pinfunction "A_A") (pintype "passive"))
      (node (ref "S16") (pin "P$1") (pinfunction "P$1_P$1") (pintype "bidirectional"))
    )
    (net (code "43") (name "Net-(D17-PadA)") (class "Default")
      (node (ref "D17") (pin "A") (pinfunction "A_A") (pintype "passive"))
      (node (ref "S17") (pin "P$1") (pinfunction "P$1_P$1") (pintype "bidirectional"))
    )
    (net (code "44") (name "Net-(D18-PadA)") (class "Default")
      (node (ref "D18") (pin "A") (pinfunction "A_A") (pintype "passive"))
      (node (ref "S18") (pin "P$1") (pinfunction "P$1_P$1") (pintype "bidirectional"))
    )
    (net (code "45") (name "Net-(D19-PadA)") (class "Default")
      (node (ref "D19") (pin "A") (pinfunction "A_A") (pintype "passive"))
      (node (ref "S19") (pin "P$1") (pinfunction "P$1_P$1") (pintype "bidirectional"))
    )
    (net (code "46") (name "Net-(D20-PadA)") (class "Default")
      (node (ref "D20") (pin "A") (pinfunction "A_A") (pintype "passive"))
      (node (ref "S20") (pin "P$1") (pinfunction "P$1_P$1") (pintype "bidirectional"))
    )
    (net (code "47") (name "Net-(D21-PadA)") (class "Default")
      (node (ref "D21") (pin "A") (pinfunction "A_A") (pintype "passive"))
      (node (ref "S21") (pin "P$1") (pinfunction "P$1_P$1") (pintype "bidirectional"))
    )
    (net (code "48") (name "Net-(D22-PadA)") (class "Default")
      (node (ref "D22") (pin "A") (pinfunction "A_A") (pintype "passive"))
      (node (ref "S22") (pin "P$1") (pinfunction "P$1_P$1") (pintype "bidirectional"))
    )
    (net (code "49") (name "Net-(D23-PadA)") (class "Default")
      (node (ref "D23") (pin "A") (pinfunction "A_A") (pintype "passive"))
      (node (ref "S23") (pin "P$1") (pinfunction "P$1_P$1") (pintype "bidirectional"))
    )
    (net (code "50") (name "Net-(D24-PadA)") (class "Default")
      (node (ref "D24") (pin "A") (pinfunction "A_A") (pintype "passive"))
      (node (ref "S24") (pin "P$1") (pinfunction "P$1_P$1") (pintype "bidirectional"))
    )
    (net (code "51") (name "Net-(D25-PadA)") (class "Default")
      (node (ref "D25") (pin "A") (pinfunction "A_A") (pintype "passive"))
      (node (ref "S25") (pin "P$1") (pinfunction "P$1_P$1") (pintype "bidirectional"))
    )
    (net (code "52") (name "Net-(D26-PadA)") (class "Default")
      (node (ref "D26") (pin "A") (pinfunction "A_A") (pintype "passive"))
      (node (ref "S26") (pin "P$1") (pinfunction "P$1_P$1") (pintype "bidirectional"))
    )
    (net (code "53") (name "Net-(D27-PadA)") (class "Default")
      (node (ref "D27") (pin "A") (pinfunction "A_A") (pintype "passive"))
      (node (ref "S27") (pin "P$1") (pinfunction "P$1_P$1") (pintype "bidirectional"))
    )
    (net (code "54") (name "Net-(D28-PadA)") (class "Default")
      (node (ref "D28") (pin "A") (pinfunction "A_A") (pintype "passive"))
      (node (ref "S28") (pin "P$1") (pinfunction "P$1_P$1") (pintype "bidirectional"))
    )
    (net (code "55") (name "Net-(D29-PadA)") (class "Default")
      (node (ref "D29") (pin "A") (pinfunction "A_A") (pintype "passive"))
      (node (ref "S29") (pin "P$1") (pinfunction "P$1_P$1") (pintype "bidirectional"))
    )
    (net (code "56") (name "Net-(D30-PadA)") (class "Default")
      (node (ref "D30") (pin "A") (pinfunction "A_A") (pintype "passive"))
      (node (ref "S30") (pin "P$1") (pinfunction "P$1_P$1") (pintype "bidirectional"))
    )
    (net (code "57") (name "Net-(D31-PadA)") (class "Default")
      (node (ref "D31") (pin "A") (pinfunction "A_A") (pintype "passive"))
      (node (ref "S31") (pin "P$1") (pinfunction "P$1_P$1") (pintype "bidirectional"))
    )
    (net (code "58") (name "Net-(D32-PadA)") (class "Default")
      (node (ref "D32") (pin "A") (pinfunction "A_A") (pintype "passive"))
      (node (ref "S32") (pin "P$1") (pinfunction "P$1_P$1") (pintype "bidirectional"))
    )
    (net (code "59") (name "Net-(D33-PadA)") (class "Default")
      (node (ref "D33") (pin "A") (pinfunction "A_A") (pintype "passive"))
      (node (ref "S33") (pin "P$1") (pinfunction "P$1_P$1") (pintype "bidirectional"))
    )
    (net (code "60") (name "Net-(D34-PadA)") (class "Default")
      (node (ref "D34") (pin "A") (pinfunction "A_A") (pintype "passive"))
      (node (ref "S34") (pin "P$1") (pinfunction "P$1_P$1") (pintype "bidirectional"))
    )
    (net (code "61") (name "Net-(D35-PadA)") (class "Default")
      (node (ref "D35") (pin "A") (pinfunction "A_A") (pintype "passive"))
      (node (ref "S35") (pin "P$1") (pinfunction "P$1_P$1") (pintype "bidirectional"))
    )
    (net (code "62") (name "Net-(D36-PadA)") (class "Default")
      (node (ref "D36") (pin "A") (pinfunction "A_A") (pintype "passive"))
      (node (ref "S36") (pin "P$1") (pinfunction "P$1_P$1") (pintype "bidirectional"))
    )
    (net (code "63") (name "Net-(D37-PadA)") (class "Default")
      (node (ref "D37") (pin "A") (pinfunction "A_A") (pintype "passive"))
      (node (ref "S37") (pin "P$1") (pinfunction "P$1_P$1") (pintype "bidirectional"))
    )
    (net (code "64") (name "Net-(D38-PadA)") (class "Default")
      (node (ref "D38") (pin "A") (pinfunction "A_A") (pintype "passive"))
      (node (ref "S38") (pin "P$1") (pinfunction "P$1_P$1") (pintype "bidirectional"))
    )
    (net (code "65") (name "Net-(D39-PadA)") (class "Default")
      (node (ref "D39") (pin "A") (pinfunction "A_A") (pintype "passive"))
      (node (ref "S39") (pin "P$1") (pinfunction "P$1_P$1") (pintype "bidirectional"))
    )
    (net (code "66") (name "Net-(D40-PadA)") (class "Default")
      (node (ref "D40") (pin "A") (pinfunction "A_A") (pintype "passive"))
      (node (ref "S40") (pin "P$1") (pinfunction "P$1_P$1") (pintype "bidirectional"))
    )
    (net (code "67") (name "Net-(D41-PadA)") (class "Default")
      (node (ref "D41") (pin "A") (pinfunction "A_A") (pintype "passive"))
      (node (ref "S41") (pin "P$1") (pinfunction "P$1_P$1") (pintype "bidirectional"))
    )
    (net (code "68") (name "Net-(D42-PadA)") (class "Default")
      (node (ref "D42") (pin "A") (pinfunction "A_A") (pintype "passive"))
      (node (ref "S42") (pin "P$1") (pinfunction "P$1_P$1") (pintype "bidirectional"))
    )
    (net (code "69") (name "Net-(D43-PadA)") (class "Default")
      (node (ref "D43") (pin "A") (pinfunction "A_A") (pintype "passive"))
      (node (ref "S43") (pin "P$1") (pinfunction "P$1_P$1") (pintype "bidirectional"))
    )
    (net (code "70") (name "Net-(D44-PadA)") (class "Default")
      (node (ref "D44") (pin "A") (pinfunction "A_A") (pintype "passive"))
      (node (ref "S44") (pin "P$1") (pinfunction "P$1_P$1") (pintype "bidirectional"))
    )
    (net (code "71") (name "Net-(D45-PadA)") (class "Default")
      (node (ref "D45") (pin "A") (pinfunction "A_A") (pintype "passive"))
      (node (ref "S45") (pin "P$1") (pinfunction "P$1_P$1") (pintype "bidirectional"))
    )
    (net (code "72") (name "Net-(D46-PadA)") (class "Default")
      (node (ref "D46") (pin "A") (pinfunction "A_A") (pintype "passive"))
      (node (ref "S46") (pin "P$1") (pinfunction "P$1_P$1") (pintype "bidirectional"))
    )
    (net (code "73") (name "Net-(D47-PadA)") (class "Default")
      (node (ref "D47") (pin "A") (pinfunction "A_A") (pintype "passive"))
      (node (ref "S47") (pin "P$1") (pinfunction "P$1_P$1") (pintype "bidirectional"))
    )
    (net (code "74") (name "Net-(D48-ANODE)") (class "Default")
      (node (ref "D48") (pin "1") (pinfunction "ANODE_1") (pintype "bidirectional"))
      (node (ref "F1") (pin "2") (pinfunction "2_2") (pintype "passive"))
    )
    (net (code "75") (name "Net-(F1-Pad1)") (class "Default")
      (node (ref "F1") (pin "1") (pinfunction "1_1") (pintype "passive"))
      (node (ref "USB1") (pin "A4/B9") (pinfunction "VBUS_A4/B9") (pintype "power_in"))
      (node (ref "USB1") (pin "B4/A9") (pinfunction "VBUS_B4/A9") (pintype "power_in"))
    )
    (net (code "76") (name "Net-(IC1-XTAL1)") (class "Default")
      (node (ref "C2") (pin "1") (pinfunction "1_1") (pintype "passive"))
      (node (ref "IC1") (pin "17") (pinfunction "XTAL1_17") (pintype "bidirectional"))
      (node (ref "Q1") (pin "X1") (pinfunction "X1_X1") (pintype "bidirectional"))
    )
    (net (code "77") (name "Net-(IC1-XTAL2)") (class "Default")
      (node (ref "C1") (pin "1") (pinfunction "1_1") (pintype "passive"))
      (node (ref "IC1") (pin "16") (pinfunction "XTAL2_16") (pintype "bidirectional"))
      (node (ref "Q1") (pin "X2") (pinfunction "X2_X2") (pintype "bidirectional"))
    )
    (net (code "78") (name "Net-(USB1-CC1)") (class "Default")
      (node (ref "R4") (pin "1") (pinfunction "1_1") (pintype "passive"))
      (node (ref "USB1") (pin "A5") (pinfunction "CC1_A5") (pintype "bidirectional"))
    )
    (net (code "79") (name "Net-(USB1-CC2)") (class "Default")
      (node (ref "R5") (pin "1") (pinfunction "1_1") (pintype "passive"))
      (node (ref "USB1") (pin "B5") (pinfunction "CC2_B5") (pintype "bidirectional"))
    )
    (net (code "80") (name "VCC") (class "Default")
      (node (ref "C4") (pin "1") (pinfunction "1_1") (pintype "passive"))
      (node (ref "C5") (pin "1") (pinfunction "1_1") (pintype "passive"))
      (node (ref "C6") (pin "1") (pinfunction "1_1") (pintype "passive"))
      (node (ref "D48") (pin "2") (pinfunction "CATHODE_2") (pintype "bidirectional"))
      (node (ref "IC1") (pin "14") (pinfunction "VCC_14") (pintype "bidirectional"))
      (node (ref "IC1") (pin "2") (pinfunction "UVCC_2") (pintype "bidirectional"))
      (node (ref "IC1") (pin "24") (pinfunction "AVCC_24") (pintype "bidirectional"))
      (node (ref "IC1") (pin "34") (pinfunction "VCC1_34") (pintype "bidirectional"))
      (node (ref "IC1") (pin "44") (pinfunction "AVCC1_44") (pintype "bidirectional"))
      (node (ref "IC1") (pin "7") (pinfunction "VBUS_7") (pintype "bidirectional"))
      (node (ref "ISP2") (pin "2") (pinfunction "VCC_2") (pintype "power_in"))
      (node (ref "R1") (pin "2") (pinfunction "2_2") (pintype "passive"))
    )
    (net (code "81") (name "unconnected-(IC1-AREF-Pad42)") (class "Default")
      (node (ref "IC1") (pin "42") (pinfunction "AREF_42") (pintype "bidirectional"))
    )
    (net (code "82") (name "unconnected-(IC1-PB0(SS)-Pad8)") (class "Default")
      (node (ref "IC1") (pin "8") (pinfunction "PB0(SS)_8") (pintype "bidirectional"))
    )
    (net (code "83") (name "unconnected-(IC1-PB7(OC0A{slash}OC1C{slash}RTS)-Pad12)") (class "Default")
      (node (ref "IC1") (pin "12") (pinfunction "PB7(OC0A/OC1C/RTS)_12") (pintype "bidirectional"))
    )
    (net (code "84") (name "unconnected-(IC1-PD0(INT0{slash}OC0B{slash}SCL)-Pad18)") (class "Default")
      (node (ref "IC1") (pin "18") (pinfunction "PD0(INT0/OC0B/SCL)_18") (pintype "bidirectional"))
    )
    (net (code "85") (name "unconnected-(IC1-PE6(INT.6{slash}AIN0)-Pad1)") (class "Default")
      (node (ref "IC1") (pin "1") (pinfunction "PE6(INT.6/AIN0)_1") (pintype "bidirectional"))
    )
    (net (code "86") (name "unconnected-(IC1-PF0(ADC0)-Pad41)") (class "Default")
      (node (ref "IC1") (pin "41") (pinfunction "PF0(ADC0)_41") (pintype "bidirectional"))
    )
    (net (code "87") (name "unconnected-(IC1-PF1(ADC1)-Pad40)") (class "Default")
      (node (ref "IC1") (pin "40") (pinfunction "PF1(ADC1)_40") (pintype "bidirectional"))
    )
    (net (code "88") (name "unconnected-(IC1-PF7(ADC7(TDI)-Pad36)") (class "Default")
      (node (ref "IC1") (pin "36") (pinfunction "PF7(ADC7(TDI)_36") (pintype "bidirectional"))
    )
    (net (code "89") (name "unconnected-(IC2-IO0-Pad1)") (class "Default")
      (node (ref "IC2") (pin "1") (pinfunction "IO0_1") (pintype "bidirectional"))
    )
    (net (code "90") (name "unconnected-(IC2-IO1-Pad3)") (class "Default")
      (node (ref "IC2") (pin "3") (pinfunction "IO1_3") (pintype "bidirectional"))
    )
    (net (code "91") (name "unconnected-(USB1-SBU1-PadA8)") (class "Default")
      (node (ref "USB1") (pin "A8") (pinfunction "SBU1_A8") (pintype "bidirectional"))
    )
    (net (code "92") (name "unconnected-(USB1-SBU2-PadB8)") (class "Default")
      (node (ref "USB1") (pin "B8") (pinfunction "SBU2_B8") (pintype "bidirectional"))
    )
  )
)
